# amp_schematic_eagle.net
KiCad netlist of a schematic drawn in EAGLE
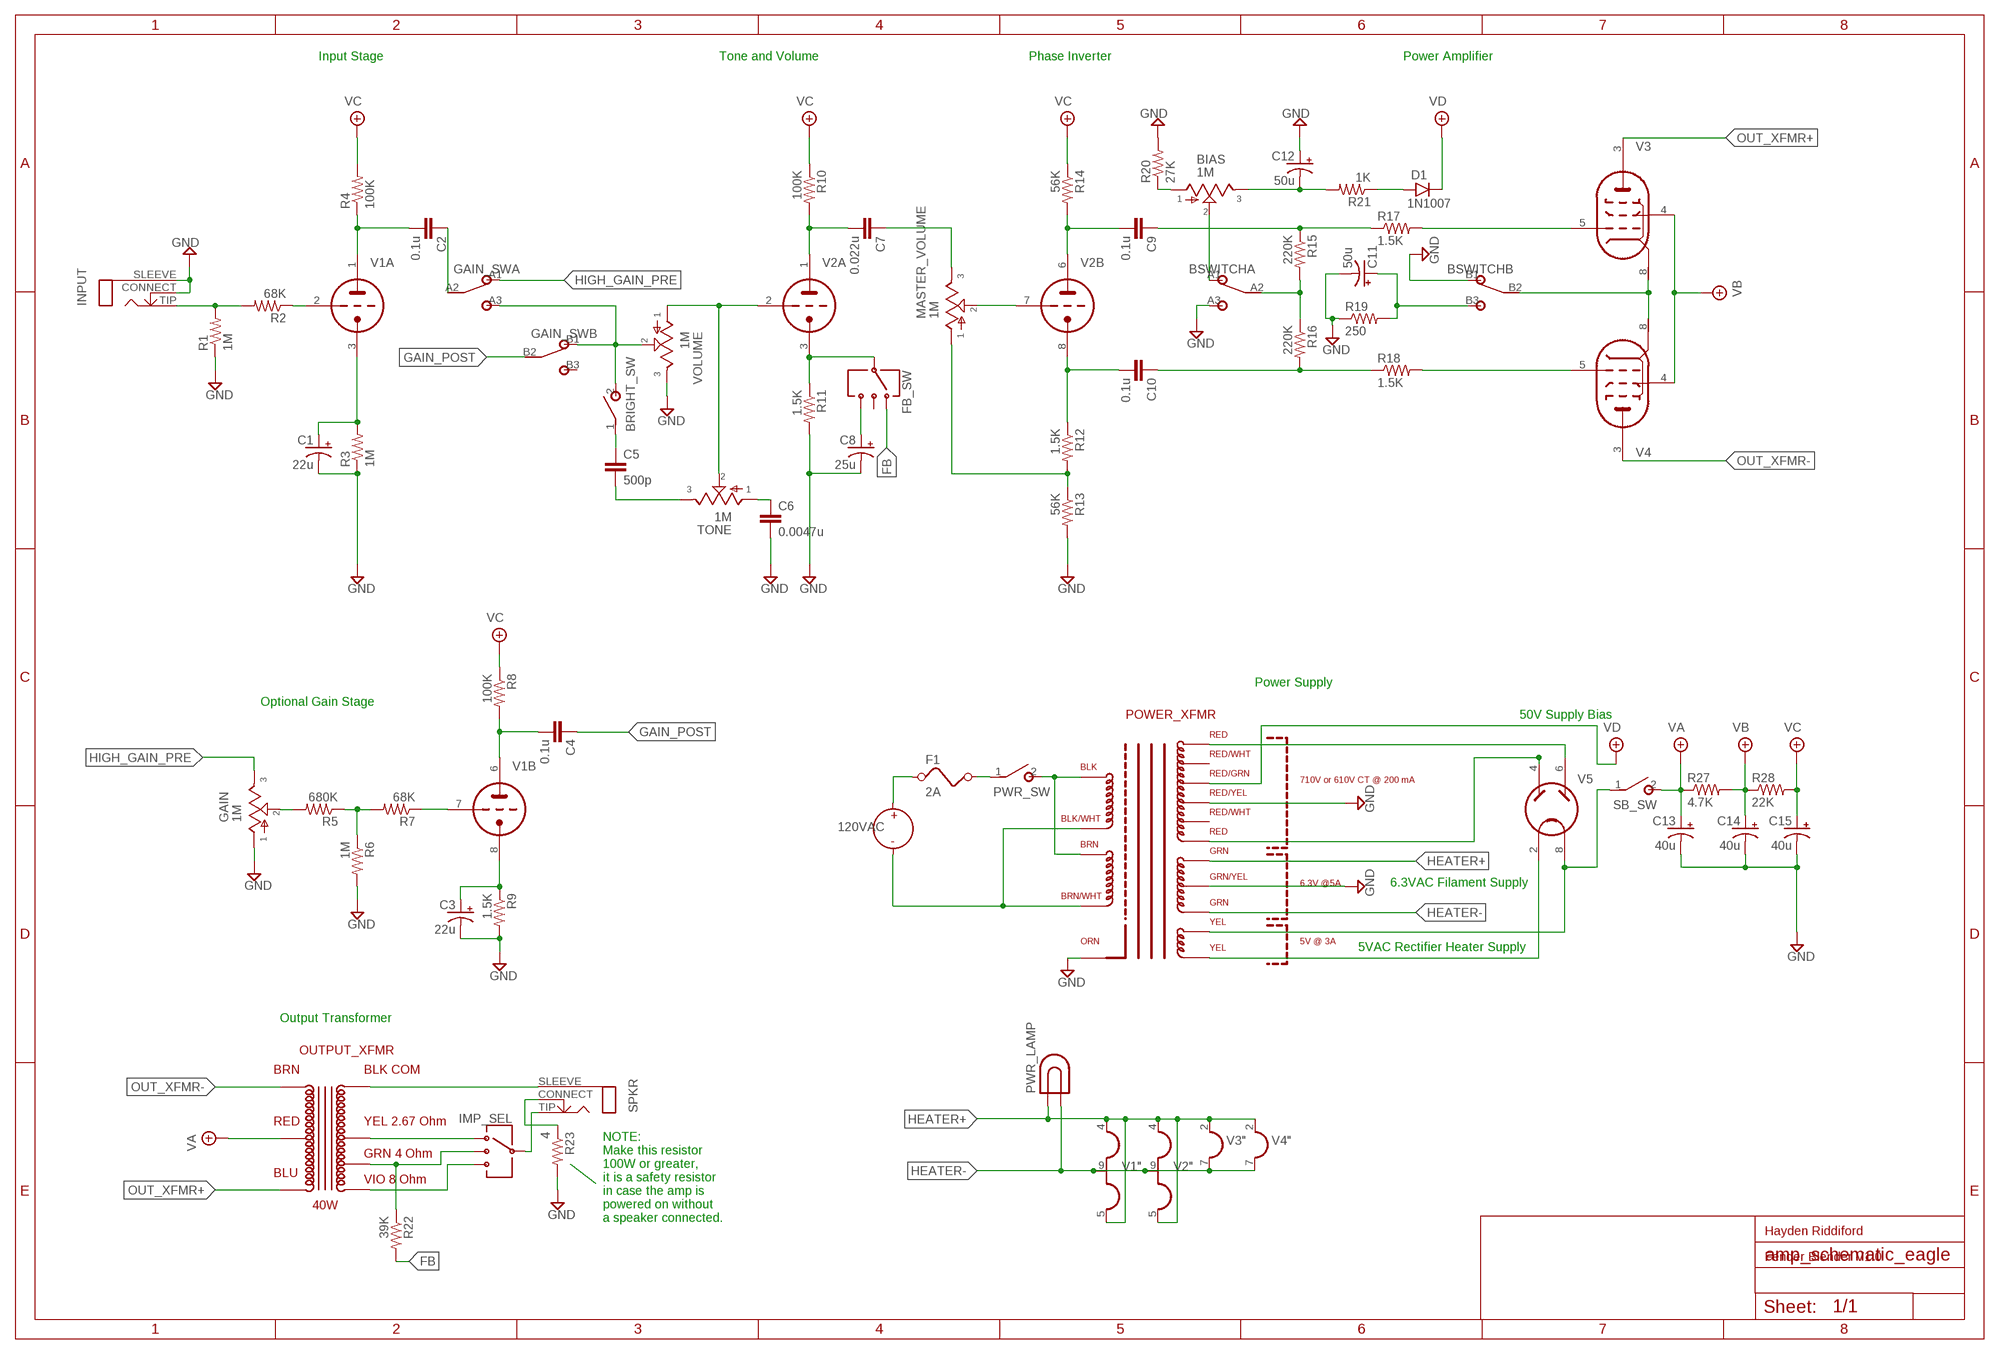
[diagram p0: schematic, sheet 1]

(export (version "E")
  (design (tool "Eeschema 10.0.6"))
  (components
    (comp (ref "BIAS")
      (value "1M")
      (footprint "eagle-import:POT")
      (libsource (lib "eagle-import") (part "POT"))
    )
    (comp (ref "BRIGHT_SW")
      (value "SPST")
      (footprint "eagle-import:SPST")
      (libsource (lib "eagle-import") (part "SPST"))
    )
    (comp (ref "BSWITCH")
      (value "DPDT")
      (footprint "eagle-import:DPDT")
      (libsource (lib "eagle-import") (part "DPDT"))
    )
    (comp (ref "C1")
      (value "22u")
      (footprint "eagle-import:050_020_4")
      (libsource (lib "eagle-import") (part "0504"))
    )
    (comp (ref "C2")
      (value "0.1u")
      (footprint "eagle-import:050X030_025_4")
      (libsource (lib "eagle-import") (part "050X030_0254"))
    )
    (comp (ref "C3")
      (value "22u")
      (footprint "eagle-import:050_020_4")
      (libsource (lib "eagle-import") (part "0504"))
    )
    (comp (ref "C4")
      (value "0.1u")
      (footprint "eagle-import:050X030_025_4")
      (libsource (lib "eagle-import") (part "050X030_0254"))
    )
    (comp (ref "C5")
      (value "500p")
      (footprint "eagle-import:050X030_025_4")
      (libsource (lib "eagle-import") (part "050X030_0254"))
    )
    (comp (ref "C6")
      (value "0.0047u")
      (footprint "eagle-import:050X030_025_4")
      (libsource (lib "eagle-import") (part "050X030_0254"))
    )
    (comp (ref "C7")
      (value "0.022u")
      (footprint "eagle-import:050X030_025_4")
      (libsource (lib "eagle-import") (part "050X030_0254"))
    )
    (comp (ref "C8")
      (value "25u")
      (footprint "eagle-import:050_020_4")
      (libsource (lib "eagle-import") (part "0504"))
    )
    (comp (ref "C9")
      (value "0.1u")
      (footprint "eagle-import:050X030_025_4")
      (libsource (lib "eagle-import") (part "050X030_0254"))
    )
    (comp (ref "C10")
      (value "0.1u")
      (footprint "eagle-import:050X030_025_4")
      (libsource (lib "eagle-import") (part "050X030_0254"))
    )
    (comp (ref "C11")
      (value "50u")
      (footprint "eagle-import:050_020_4")
      (libsource (lib "eagle-import") (part "0504"))
    )
    (comp (ref "C12")
      (value "50u")
      (footprint "eagle-import:050_020_4")
      (libsource (lib "eagle-import") (part "0504"))
    )
    (comp (ref "C13")
      (value "40u")
      (footprint "eagle-import:050_020_4")
      (libsource (lib "eagle-import") (part "0504"))
    )
    (comp (ref "C14")
      (value "40u")
      (footprint "eagle-import:050_020_4")
      (libsource (lib "eagle-import") (part "0504"))
    )
    (comp (ref "C15")
      (value "40u")
      (footprint "eagle-import:050_020_4")
      (libsource (lib "eagle-import") (part "0504"))
    )
    (comp (ref "D1")
      (value "1N1007")
      (footprint "eagle-import:DO07")
      (libsource (lib "eagle-import") (part "DO07"))
    )
    (comp (ref "F1")
      (value "2A")
      (footprint "eagle-import:FUSE")
      (libsource (lib "eagle-import") (part "FUSE"))
    )
    (comp (ref "FB_SW")
      (value "SWITCH-SP3T")
      (footprint "eagle-import:SWITCH-SP3T-SMD")
      (libsource (lib "eagle-import") (part "SWITCH-SP3T"))
    )
    (comp (ref "GAIN")
      (value "1M")
      (footprint "eagle-import:POT")
      (libsource (lib "eagle-import") (part "POT"))
    )
    (comp (ref "GAIN_SW")
      (value "DPDT")
      (footprint "eagle-import:DPDT")
      (libsource (lib "eagle-import") (part "DPDT"))
    )
    (comp (ref "IMP_SEL")
      (value "SWITCH-SP3T")
      (footprint "eagle-import:SWITCH-SP3T-SMD")
      (libsource (lib "eagle-import") (part "SWITCH-SP3T"))
    )
    (comp (ref "INPUT")
      (value "CLOSEDMONO")
      (footprint "eagle-import:CLOSED_MONO_JACK")
      (libsource (lib "eagle-import") (part "CLOSEDMONO"))
    )
    (comp (ref "MASTER_VOLUME")
      (value "1M")
      (footprint "eagle-import:POT")
      (libsource (lib "eagle-import") (part "POT"))
    )
    (comp (ref "OUTPUT_XFMR")
      (value "CLASSIC_TONE_40-18088")
      (footprint "eagle-import:CLASSIC_TONE_40-18088")
      (libsource (lib "eagle-import") (part "CLASSIC_TONE_40-18088"))
    )
    (comp (ref "POWER_XFMR")
      (value "CLASSIC_TONE_40-18094")
      (footprint "eagle-import:CLASSIC_TONE_40-18094")
      (libsource (lib "eagle-import") (part "CLASSIC_TONE_40-18094"))
    )
    (comp (ref "PWR_LAMP")
      (value "LAMP")
      (footprint "eagle-import:LDH-5R")
      (libsource (lib "eagle-import") (part "LAMP"))
    )
    (comp (ref "PWR_SW")
      (value "SPST")
      (footprint "eagle-import:SPST")
      (libsource (lib "eagle-import") (part "SPST"))
    )
    (comp (ref "R1")
      (value "1M")
      (footprint "eagle-import:R0207_2V")
      (libsource (lib "eagle-import") (part "6MM.2"))
    )
    (comp (ref "R2")
      (value "68K")
      (footprint "eagle-import:R0207_2V")
      (libsource (lib "eagle-import") (part "6MM.2"))
    )
    (comp (ref "R3")
      (value "1M")
      (footprint "eagle-import:R0207_2V")
      (libsource (lib "eagle-import") (part "6MM.2"))
    )
    (comp (ref "R4")
      (value "100K")
      (footprint "eagle-import:R0207_2V")
      (libsource (lib "eagle-import") (part "6MM.2"))
    )
    (comp (ref "R5")
      (value "680K")
      (footprint "eagle-import:R0207_2V")
      (libsource (lib "eagle-import") (part "6MM.2"))
    )
    (comp (ref "R6")
      (value "1M")
      (footprint "eagle-import:R0207_2V")
      (libsource (lib "eagle-import") (part "6MM.2"))
    )
    (comp (ref "R7")
      (value "68K")
      (footprint "eagle-import:R0207_2V")
      (libsource (lib "eagle-import") (part "6MM.2"))
    )
    (comp (ref "R8")
      (value "100K")
      (footprint "eagle-import:R0207_2V")
      (libsource (lib "eagle-import") (part "6MM.2"))
    )
    (comp (ref "R9")
      (value "1.5K")
      (footprint "eagle-import:R0207_2V")
      (libsource (lib "eagle-import") (part "6MM.2"))
    )
    (comp (ref "R10")
      (value "100K")
      (footprint "eagle-import:R0207_2V")
      (libsource (lib "eagle-import") (part "6MM.2"))
    )
    (comp (ref "R11")
      (value "1.5K")
      (footprint "eagle-import:R0207_2V")
      (libsource (lib "eagle-import") (part "6MM.2"))
    )
    (comp (ref "R12")
      (value "1.5K")
      (footprint "eagle-import:R0207_2V")
      (libsource (lib "eagle-import") (part "6MM.2"))
    )
    (comp (ref "R13")
      (value "56K")
      (footprint "eagle-import:R0207_2V")
      (libsource (lib "eagle-import") (part "6MM.2"))
    )
    (comp (ref "R14")
      (value "56K")
      (footprint "eagle-import:R0207_2V")
      (libsource (lib "eagle-import") (part "6MM.2"))
    )
    (comp (ref "R15")
      (value "220K")
      (footprint "eagle-import:R0207_2V")
      (libsource (lib "eagle-import") (part "6MM.2"))
    )
    (comp (ref "R16")
      (value "220K")
      (footprint "eagle-import:R0207_2V")
      (libsource (lib "eagle-import") (part "6MM.2"))
    )
    (comp (ref "R17")
      (value "1.5K")
      (footprint "eagle-import:R0207_2V")
      (libsource (lib "eagle-import") (part "6MM.2"))
    )
    (comp (ref "R18")
      (value "1.5K")
      (footprint "eagle-import:R0207_2V")
      (libsource (lib "eagle-import") (part "6MM.2"))
    )
    (comp (ref "R19")
      (value "250")
      (footprint "eagle-import:R0207_2V")
      (libsource (lib "eagle-import") (part "6MM.2"))
    )
    (comp (ref "R20")
      (value "27K")
      (footprint "eagle-import:R0207_2V")
      (libsource (lib "eagle-import") (part "6MM.2"))
    )
    (comp (ref "R21")
      (value "1K")
      (footprint "eagle-import:R0207_2V")
      (libsource (lib "eagle-import") (part "6MM.2"))
    )
    (comp (ref "R22")
      (value "39K")
      (footprint "eagle-import:R0207_2V")
      (libsource (lib "eagle-import") (part "6MM.2"))
    )
    (comp (ref "R23")
      (value "4")
      (footprint "eagle-import:R0207_2V")
      (libsource (lib "eagle-import") (part "6MM.2"))
    )
    (comp (ref "R27")
      (value "4.7K")
      (footprint "eagle-import:R0207_2V")
      (libsource (lib "eagle-import") (part "6MM.2"))
    )
    (comp (ref "R28")
      (value "22K")
      (footprint "eagle-import:R0207_2V")
      (libsource (lib "eagle-import") (part "6MM.2"))
    )
    (comp (ref "SB_SW")
      (value "SPST")
      (footprint "eagle-import:SPST")
      (libsource (lib "eagle-import") (part "SPST"))
    )
    (comp (ref "SPKR")
      (value "CLOSEDMONO")
      (footprint "eagle-import:CLOSED_MONO_JACK")
      (libsource (lib "eagle-import") (part "CLOSEDMONO"))
    )
    (comp (ref "TONE")
      (value "1M")
      (footprint "eagle-import:POT")
      (libsource (lib "eagle-import") (part "POT"))
    )
    (comp (ref "V1")
      (value "12AX7-P")
      (footprint "eagle-import:NOVAL")
      (libsource (lib "eagle-import") (part "12AX7-P"))
    )
    (comp (ref "V2")
      (value "12AX7-P")
      (footprint "eagle-import:NOVAL")
      (libsource (lib "eagle-import") (part "12AX7-P"))
    )
    (comp (ref "V3")
      (value "6V6GT-P")
      (footprint "eagle-import:OKTAL")
      (libsource (lib "eagle-import") (part "6V6GT-P"))
    )
    (comp (ref "V4")
      (value "6V6GT-P")
      (footprint "eagle-import:OKTAL")
      (libsource (lib "eagle-import") (part "6V6GT-P"))
    )
    (comp (ref "V5")
      (value "5Y3GT")
      (footprint "eagle-import:OKTAL")
      (libsource (lib "eagle-import") (part "5Y3GT"))
    )
    (comp (ref "VOLUME")
      (value "1M")
      (footprint "eagle-import:POT")
      (libsource (lib "eagle-import") (part "POT"))
    )
  )
  (nets
    (net (code "1") (name "FB") (class "Default")
      (node (ref "FB_SW") (pin "1") (pinfunction "1_1") (pintype "bidirectional"))
      (node (ref "R22") (pin "2") (pinfunction "2_2") (pintype "passive"))
    )
    (net (code "2") (name "GAIN_POST") (class "Default")
      (node (ref "C4") (pin "1") (pinfunction "1_1") (pintype "passive"))
      (node (ref "GAIN_SW") (pin "B2") (pinfunction "2_B2") (pintype "passive"))
    )
    (net (code "3") (name "GND") (class "Default")
      (node (ref "BSWITCH") (pin "A3") (pinfunction "3_A3") (pintype "passive"))
      (node (ref "BSWITCH") (pin "B1") (pinfunction "1_B1") (pintype "passive"))
      (node (ref "C1") (pin "-") (pinfunction "-_-") (pintype "passive"))
      (node (ref "C11") (pin "-") (pinfunction "-_-") (pintype "passive"))
      (node (ref "C12") (pin "+") (pinfunction "+_+") (pintype "passive"))
      (node (ref "C13") (pin "-") (pinfunction "-_-") (pintype "passive"))
      (node (ref "C14") (pin "-") (pinfunction "-_-") (pintype "passive"))
      (node (ref "C15") (pin "-") (pinfunction "-_-") (pintype "passive"))
      (node (ref "C3") (pin "-") (pinfunction "-_-") (pintype "passive"))
      (node (ref "C6") (pin "2") (pinfunction "2_2") (pintype "passive"))
      (node (ref "C8") (pin "-") (pinfunction "-_-") (pintype "passive"))
      (node (ref "GAIN") (pin "1") (pinfunction "1_1") (pintype "passive"))
      (node (ref "INPUT") (pin "CONNECT") (pinfunction "CONNECT_CONNECT") (pintype "passive"))
      (node (ref "INPUT") (pin "SLEEVE") (pinfunction "RING_SLEEVE") (pintype "passive"))
      (node (ref "POWER_XFMR") (pin "P$12") (pinfunction "P$12_P$12") (pintype "bidirectional"))
      (node (ref "POWER_XFMR") (pin "P$16") (pinfunction "P$16_P$16") (pintype "bidirectional"))
      (node (ref "POWER_XFMR") (pin "P$8") (pinfunction "P$8_P$8") (pintype "bidirectional"))
      (node (ref "R1") (pin "1") (pinfunction "1_1") (pintype "passive"))
      (node (ref "R11") (pin "2") (pinfunction "2_2") (pintype "passive"))
      (node (ref "R13") (pin "2") (pinfunction "2_2") (pintype "passive"))
      (node (ref "R19") (pin "1") (pinfunction "1_1") (pintype "passive"))
      (node (ref "R20") (pin "2") (pinfunction "2_2") (pintype "passive"))
      (node (ref "R23") (pin "2") (pinfunction "2_2") (pintype "passive"))
      (node (ref "R3") (pin "1") (pinfunction "1_1") (pintype "passive"))
      (node (ref "R6") (pin "2") (pinfunction "2_2") (pintype "passive"))
      (node (ref "R9") (pin "2") (pinfunction "2_2") (pintype "passive"))
      (node (ref "VOLUME") (pin "3") (pinfunction "3_3") (pintype "passive"))
    )
    (net (code "4") (name "HEATER+") (class "Default")
      (node (ref "POWER_XFMR") (pin "P$11") (pinfunction "P$11_P$11") (pintype "bidirectional"))
      (node (ref "PWR_LAMP") (pin "1") (pinfunction "1_1") (pintype "passive"))
      (node (ref "V1") (pin "4") (pinfunction "H1_4") (pintype "passive"))
      (node (ref "V1") (pin "5") (pinfunction "H3_5") (pintype "passive"))
      (node (ref "V2") (pin "4") (pinfunction "H1_4") (pintype "passive"))
      (node (ref "V2") (pin "5") (pinfunction "H3_5") (pintype "passive"))
      (node (ref "V3") (pin "2") (pinfunction "H1_2") (pintype "passive"))
      (node (ref "V4") (pin "2") (pinfunction "H1_2") (pintype "passive"))
    )
    (net (code "5") (name "HEATER-") (class "Default")
      (node (ref "POWER_XFMR") (pin "P$13") (pinfunction "P$13_P$13") (pintype "bidirectional"))
      (node (ref "PWR_LAMP") (pin "2") (pinfunction "2_2") (pintype "passive"))
      (node (ref "V1") (pin "9") (pinfunction "H2_9") (pintype "passive"))
      (node (ref "V2") (pin "9") (pinfunction "H2_9") (pintype "passive"))
      (node (ref "V3") (pin "7") (pinfunction "H2_7") (pintype "passive"))
      (node (ref "V4") (pin "7") (pinfunction "H2_7") (pintype "passive"))
    )
    (net (code "6") (name "HIGH_GAIN_PRE") (class "Default")
      (node (ref "GAIN") (pin "3") (pinfunction "3_3") (pintype "passive"))
      (node (ref "GAIN_SW") (pin "A1") (pinfunction "1_A1") (pintype "passive"))
    )
    (net (code "7") (name "Net-(BIAS-Pad1)") (class "Default")
      (node (ref "BIAS") (pin "1") (pinfunction "1_1") (pintype "passive"))
      (node (ref "R20") (pin "1") (pinfunction "1_1") (pintype "passive"))
    )
    (net (code "8") (name "Net-(BIAS-Pad3)") (class "Default")
      (node (ref "BIAS") (pin "3") (pinfunction "3_3") (pintype "passive"))
      (node (ref "C12") (pin "-") (pinfunction "-_-") (pintype "passive"))
      (node (ref "R21") (pin "2") (pinfunction "2_2") (pintype "passive"))
    )
    (net (code "9") (name "Net-(BRIGHT_SW-P)") (class "Default")
      (node (ref "BRIGHT_SW") (pin "1") (pinfunction "P_1") (pintype "passive"))
      (node (ref "C5") (pin "1") (pinfunction "1_1") (pintype "passive"))
    )
    (net (code "10") (name "Net-(BRIGHT_SW-S)") (class "Default")
      (node (ref "BRIGHT_SW") (pin "2") (pinfunction "S_2") (pintype "passive"))
      (node (ref "GAIN_SW") (pin "A3") (pinfunction "3_A3") (pintype "passive"))
      (node (ref "GAIN_SW") (pin "B1") (pinfunction "1_B1") (pintype "passive"))
      (node (ref "VOLUME") (pin "2") (pinfunction "2_2") (pintype "passive"))
    )
    (net (code "11") (name "Net-(BSWITCHA-1)") (class "Default")
      (node (ref "BIAS") (pin "2") (pinfunction "2_2") (pintype "passive"))
      (node (ref "BSWITCH") (pin "A1") (pinfunction "1_A1") (pintype "passive"))
    )
    (net (code "12") (name "Net-(BSWITCHA-2)") (class "Default")
      (node (ref "BSWITCH") (pin "A2") (pinfunction "2_A2") (pintype "passive"))
      (node (ref "R15") (pin "2") (pinfunction "2_2") (pintype "passive"))
      (node (ref "R16") (pin "1") (pinfunction "1_1") (pintype "passive"))
    )
    (net (code "13") (name "Net-(BSWITCHB-2)") (class "Default")
      (node (ref "BSWITCH") (pin "B2") (pinfunction "2_B2") (pintype "passive"))
      (node (ref "V3") (pin "8") (pinfunction "PK_8") (pintype "passive"))
      (node (ref "V4") (pin "8") (pinfunction "PK_8") (pintype "passive"))
    )
    (net (code "14") (name "Net-(BSWITCHB-3)") (class "Default")
      (node (ref "BSWITCH") (pin "B3") (pinfunction "3_B3") (pintype "passive"))
      (node (ref "C11") (pin "+") (pinfunction "+_+") (pintype "passive"))
      (node (ref "R19") (pin "2") (pinfunction "2_2") (pintype "passive"))
    )
    (net (code "15") (name "Net-(C5-Pad2)") (class "Default")
      (node (ref "C5") (pin "2") (pinfunction "2_2") (pintype "passive"))
      (node (ref "TONE") (pin "3") (pinfunction "3_3") (pintype "passive"))
    )
    (net (code "16") (name "Net-(C6-Pad1)") (class "Default")
      (node (ref "C6") (pin "1") (pinfunction "1_1") (pintype "passive"))
      (node (ref "TONE") (pin "1") (pinfunction "1_1") (pintype "passive"))
    )
    (net (code "17") (name "Net-(C7-Pad1)") (class "Default")
      (node (ref "C7") (pin "1") (pinfunction "1_1") (pintype "passive"))
      (node (ref "MASTER_VOLUME") (pin "3") (pinfunction "3_3") (pintype "passive"))
    )
    (net (code "18") (name "Net-(C8-Pad+)") (class "Default")
      (node (ref "C8") (pin "+") (pinfunction "+_+") (pintype "passive"))
      (node (ref "FB_SW") (pin "4") (pinfunction "4_4") (pintype "bidirectional"))
    )
    (net (code "19") (name "Net-(C9-Pad1)") (class "Default")
      (node (ref "C9") (pin "1") (pinfunction "1_1") (pintype "passive"))
      (node (ref "R15") (pin "1") (pinfunction "1_1") (pintype "passive"))
      (node (ref "R17") (pin "1") (pinfunction "1_1") (pintype "passive"))
    )
    (net (code "20") (name "Net-(C10-Pad1)") (class "Default")
      (node (ref "C10") (pin "1") (pinfunction "1_1") (pintype "passive"))
      (node (ref "R16") (pin "2") (pinfunction "2_2") (pintype "passive"))
      (node (ref "R18") (pin "1") (pinfunction "1_1") (pintype "passive"))
    )
    (net (code "21") (name "Net-(D1-PadA)") (class "Default")
      (node (ref "D1") (pin "A") (pinfunction "A_A") (pintype "passive"))
      (node (ref "R21") (pin "1") (pinfunction "1_1") (pintype "passive"))
    )
    (net (code "22") (name "Net-(F1-Pad1)") (class "Default")
      (node (ref "F1") (pin "1") (pinfunction "1_1") (pintype "passive"))
    )
    (net (code "23") (name "Net-(GAIN-Pad2)") (class "Default")
      (node (ref "GAIN") (pin "2") (pinfunction "2_2") (pintype "passive"))
      (node (ref "R5") (pin "2") (pinfunction "2_2") (pintype "passive"))
    )
    (net (code "24") (name "Net-(GAIN_SWA-2)") (class "Default")
      (node (ref "C2") (pin "1") (pinfunction "1_1") (pintype "passive"))
      (node (ref "GAIN_SW") (pin "A2") (pinfunction "2_A2") (pintype "passive"))
    )
    (net (code "25") (name "Net-(IMP_SEL-Pad1)") (class "Default")
      (node (ref "IMP_SEL") (pin "1") (pinfunction "1_1") (pintype "bidirectional"))
      (node (ref "OUTPUT_XFMR") (pin "P$5") (pinfunction "P$5_P$5") (pintype "bidirectional"))
    )
    (net (code "26") (name "Net-(IMP_SEL-Pad2)") (class "Default")
      (node (ref "IMP_SEL") (pin "2") (pinfunction "2_2") (pintype "bidirectional"))
      (node (ref "OUTPUT_XFMR") (pin "P$6") (pinfunction "P$6_P$6") (pintype "bidirectional"))
      (node (ref "R22") (pin "1") (pinfunction "1_1") (pintype "passive"))
    )
    (net (code "27") (name "Net-(IMP_SEL-Pad3)") (class "Default")
      (node (ref "IMP_SEL") (pin "3") (pinfunction "3_3") (pintype "bidirectional"))
      (node (ref "SPKR") (pin "TIP") (pinfunction "TIP_TIP") (pintype "passive"))
    )
    (net (code "28") (name "Net-(IMP_SEL-Pad4)") (class "Default")
      (node (ref "IMP_SEL") (pin "4") (pinfunction "4_4") (pintype "bidirectional"))
      (node (ref "OUTPUT_XFMR") (pin "P$7") (pinfunction "P$7_P$7") (pintype "bidirectional"))
    )
    (net (code "29") (name "Net-(INPUT-PadTIP)") (class "Default")
      (node (ref "INPUT") (pin "TIP") (pinfunction "TIP_TIP") (pintype "passive"))
      (node (ref "R1") (pin "2") (pinfunction "2_2") (pintype "passive"))
      (node (ref "R2") (pin "2") (pinfunction "2_2") (pintype "passive"))
    )
    (net (code "30") (name "Net-(MASTER_VOLUME-Pad1)") (class "Default")
      (node (ref "MASTER_VOLUME") (pin "1") (pinfunction "1_1") (pintype "passive"))
      (node (ref "R12") (pin "2") (pinfunction "2_2") (pintype "passive"))
      (node (ref "R13") (pin "1") (pinfunction "1_1") (pintype "passive"))
    )
    (net (code "31") (name "Net-(POWER_XFMR-PadP$2)") (class "Default")
      (node (ref "POWER_XFMR") (pin "P$2") (pinfunction "P$2_P$2") (pintype "bidirectional"))
      (node (ref "POWER_XFMR") (pin "P$4") (pinfunction "P$4_P$4") (pintype "bidirectional"))
    )
    (net (code "32") (name "Net-(PWR_SW-P)") (class "Default")
      (node (ref "F1") (pin "2") (pinfunction "2_2") (pintype "passive"))
      (node (ref "PWR_SW") (pin "1") (pinfunction "P_1") (pintype "passive"))
    )
    (net (code "33") (name "Net-(PWR_SW-S)") (class "Default")
      (node (ref "POWER_XFMR") (pin "P$1") (pinfunction "P$1_P$1") (pintype "bidirectional"))
      (node (ref "POWER_XFMR") (pin "P$3") (pinfunction "P$3_P$3") (pintype "bidirectional"))
      (node (ref "PWR_SW") (pin "2") (pinfunction "S_2") (pintype "passive"))
    )
    (net (code "34") (name "Net-(R5-Pad1)") (class "Default")
      (node (ref "R5") (pin "1") (pinfunction "1_1") (pintype "passive"))
      (node (ref "R6") (pin "1") (pinfunction "1_1") (pintype "passive"))
      (node (ref "R7") (pin "2") (pinfunction "2_2") (pintype "passive"))
    )
    (net (code "35") (name "Net-(R23-Pad1)") (class "Default")
      (node (ref "R23") (pin "1") (pinfunction "1_1") (pintype "passive"))
      (node (ref "SPKR") (pin "CONNECT") (pinfunction "CONNECT_CONNECT") (pintype "passive"))
    )
    (net (code "36") (name "Net-(SB_SW-P)") (class "Default")
      (node (ref "POWER_XFMR") (pin "P$14") (pinfunction "P$14_P$14") (pintype "bidirectional"))
      (node (ref "SB_SW") (pin "1") (pinfunction "P_1") (pintype "passive"))
      (node (ref "V5") (pin "8") (pinfunction "H2_8") (pintype "passive"))
    )
    (net (code "37") (name "Net-(SPKR-RING)") (class "Default")
      (node (ref "OUTPUT_XFMR") (pin "P$4") (pinfunction "P$4_P$4") (pintype "bidirectional"))
      (node (ref "SPKR") (pin "SLEEVE") (pinfunction "RING_SLEEVE") (pintype "passive"))
    )
    (net (code "38") (name "Net-(V1B-TA)") (class "Default")
      (node (ref "C2") (pin "2") (pinfunction "2_2") (pintype "passive"))
      (node (ref "R4") (pin "1") (pinfunction "1_1") (pintype "passive"))
      (node (ref "V1") (pin "1") (pinfunction "TA_1") (pintype "passive"))
    )
    (net (code "39") (name "Net-(V1B-TG)") (class "Default")
      (node (ref "R2") (pin "1") (pinfunction "1_1") (pintype "passive"))
      (node (ref "V1") (pin "2") (pinfunction "TG_2") (pintype "passive"))
    )
    (net (code "40") (name "Net-(V1B-TK)") (class "Default")
      (node (ref "C1") (pin "+") (pinfunction "+_+") (pintype "passive"))
      (node (ref "R3") (pin "2") (pinfunction "2_2") (pintype "passive"))
      (node (ref "V1") (pin "3") (pinfunction "TK_3") (pintype "passive"))
    )
    (net (code "41") (name "Net-(V1C-TA)") (class "Default")
      (node (ref "C4") (pin "2") (pinfunction "2_2") (pintype "passive"))
      (node (ref "R8") (pin "2") (pinfunction "2_2") (pintype "passive"))
      (node (ref "V1") (pin "6") (pinfunction "TA_6") (pintype "passive"))
    )
    (net (code "42") (name "Net-(V1C-TG)") (class "Default")
      (node (ref "R7") (pin "1") (pinfunction "1_1") (pintype "passive"))
      (node (ref "V1") (pin "7") (pinfunction "TG_7") (pintype "passive"))
    )
    (net (code "43") (name "Net-(V1C-TK)") (class "Default")
      (node (ref "C3") (pin "+") (pinfunction "+_+") (pintype "passive"))
      (node (ref "R9") (pin "1") (pinfunction "1_1") (pintype "passive"))
      (node (ref "V1") (pin "8") (pinfunction "TK_8") (pintype "passive"))
    )
    (net (code "44") (name "Net-(V2B-TA)") (class "Default")
      (node (ref "C7") (pin "2") (pinfunction "2_2") (pintype "passive"))
      (node (ref "R10") (pin "2") (pinfunction "2_2") (pintype "passive"))
      (node (ref "V2") (pin "1") (pinfunction "TA_1") (pintype "passive"))
    )
    (net (code "45") (name "Net-(V2B-TG)") (class "Default")
      (node (ref "TONE") (pin "2") (pinfunction "2_2") (pintype "passive"))
      (node (ref "V2") (pin "2") (pinfunction "TG_2") (pintype "passive"))
      (node (ref "VOLUME") (pin "1") (pinfunction "1_1") (pintype "passive"))
    )
    (net (code "46") (name "Net-(V2B-TK)") (class "Default")
      (node (ref "FB_SW") (pin "3") (pinfunction "3_3") (pintype "bidirectional"))
      (node (ref "R11") (pin "1") (pinfunction "1_1") (pintype "passive"))
      (node (ref "V2") (pin "3") (pinfunction "TK_3") (pintype "passive"))
    )
    (net (code "47") (name "Net-(V2C-TA)") (class "Default")
      (node (ref "C9") (pin "2") (pinfunction "2_2") (pintype "passive"))
      (node (ref "R14") (pin "2") (pinfunction "2_2") (pintype "passive"))
      (node (ref "V2") (pin "6") (pinfunction "TA_6") (pintype "passive"))
    )
    (net (code "48") (name "Net-(V2C-TG)") (class "Default")
      (node (ref "MASTER_VOLUME") (pin "2") (pinfunction "2_2") (pintype "passive"))
      (node (ref "V2") (pin "7") (pinfunction "TG_7") (pintype "passive"))
    )
    (net (code "49") (name "Net-(V2C-TK)") (class "Default")
      (node (ref "C10") (pin "2") (pinfunction "2_2") (pintype "passive"))
      (node (ref "R12") (pin "1") (pinfunction "1_1") (pintype "passive"))
      (node (ref "V2") (pin "8") (pinfunction "TK_8") (pintype "passive"))
    )
    (net (code "50") (name "Net-(V3B-PG)") (class "Default")
      (node (ref "R17") (pin "2") (pinfunction "2_2") (pintype "passive"))
      (node (ref "V3") (pin "5") (pinfunction "PG_5") (pintype "passive"))
    )
    (net (code "51") (name "Net-(V4B-PG)") (class "Default")
      (node (ref "R18") (pin "2") (pinfunction "2_2") (pintype "passive"))
      (node (ref "V4") (pin "5") (pinfunction "PG_5") (pintype "passive"))
    )
    (net (code "52") (name "Net-(V5-A1)") (class "Default")
      (node (ref "POWER_XFMR") (pin "P$10") (pinfunction "P$10_P$10") (pintype "bidirectional"))
      (node (ref "V5") (pin "4") (pinfunction "A1_4") (pintype "passive"))
    )
    (net (code "53") (name "Net-(V5-A2)") (class "Default")
      (node (ref "POWER_XFMR") (pin "P$5") (pinfunction "P$5_P$5") (pintype "bidirectional"))
      (node (ref "V5") (pin "6") (pinfunction "A2_6") (pintype "passive"))
    )
    (net (code "54") (name "Net-(V5-H1)") (class "Default")
      (node (ref "POWER_XFMR") (pin "P$15") (pinfunction "P$15_P$15") (pintype "bidirectional"))
      (node (ref "V5") (pin "2") (pinfunction "H1_2") (pintype "passive"))
    )
    (net (code "55") (name "OUT_XFMR+") (class "Default")
      (node (ref "OUTPUT_XFMR") (pin "P$3") (pinfunction "P$3_P$3") (pintype "bidirectional"))
      (node (ref "V3") (pin "3") (pinfunction "PA_3") (pintype "passive"))
    )
    (net (code "56") (name "OUT_XFMR-") (class "Default")
      (node (ref "OUTPUT_XFMR") (pin "P$1") (pinfunction "P$1_P$1") (pintype "bidirectional"))
      (node (ref "V4") (pin "3") (pinfunction "PA_3") (pintype "passive"))
    )
    (net (code "57") (name "VA") (class "Default")
      (node (ref "C13") (pin "+") (pinfunction "+_+") (pintype "passive"))
      (node (ref "OUTPUT_XFMR") (pin "P$2") (pinfunction "P$2_P$2") (pintype "bidirectional"))
      (node (ref "R27") (pin "1") (pinfunction "1_1") (pintype "passive"))
      (node (ref "SB_SW") (pin "2") (pinfunction "S_2") (pintype "passive"))
    )
    (net (code "58") (name "VB") (class "Default")
      (node (ref "C14") (pin "+") (pinfunction "+_+") (pintype "passive"))
      (node (ref "R27") (pin "2") (pinfunction "2_2") (pintype "passive"))
      (node (ref "R28") (pin "1") (pinfunction "1_1") (pintype "passive"))
      (node (ref "V3") (pin "4") (pinfunction "PSG_4") (pintype "passive"))
      (node (ref "V4") (pin "4") (pinfunction "PSG_4") (pintype "passive"))
    )
    (net (code "59") (name "VC") (class "Default")
      (node (ref "C15") (pin "+") (pinfunction "+_+") (pintype "passive"))
      (node (ref "R10") (pin "1") (pinfunction "1_1") (pintype "passive"))
      (node (ref "R14") (pin "1") (pinfunction "1_1") (pintype "passive"))
      (node (ref "R28") (pin "2") (pinfunction "2_2") (pintype "passive"))
      (node (ref "R4") (pin "2") (pinfunction "2_2") (pintype "passive"))
      (node (ref "R8") (pin "1") (pinfunction "1_1") (pintype "passive"))
    )
    (net (code "60") (name "VD") (class "Default")
      (node (ref "D1") (pin "C") (pinfunction "C_C") (pintype "passive"))
      (node (ref "POWER_XFMR") (pin "P$7") (pinfunction "P$7_P$7") (pintype "bidirectional"))
    )
    (net (code "61") (name "unconnected-(FB_SW-Pad2)") (class "Default")
      (node (ref "FB_SW") (pin "2") (pinfunction "2_2") (pintype "bidirectional"))
    )
    (net (code "62") (name "unconnected-(GAIN_SWB-3-PadB3)") (class "Default")
      (node (ref "GAIN_SW") (pin "B3") (pinfunction "3_B3") (pintype "passive"))
    )
    (net (code "63") (name "unconnected-(POWER_XFMR-PadP$6)") (class "Default")
      (node (ref "POWER_XFMR") (pin "P$6") (pinfunction "P$6_P$6") (pintype "bidirectional"))
    )
    (net (code "64") (name "unconnected-(POWER_XFMR-PadP$9)") (class "Default")
      (node (ref "POWER_XFMR") (pin "P$9") (pinfunction "P$9_P$9") (pintype "bidirectional"))
    )
  )
)
